# Test_board_-_MCP73871.net
KiCad netlist of a schematic drawn in EAGLE
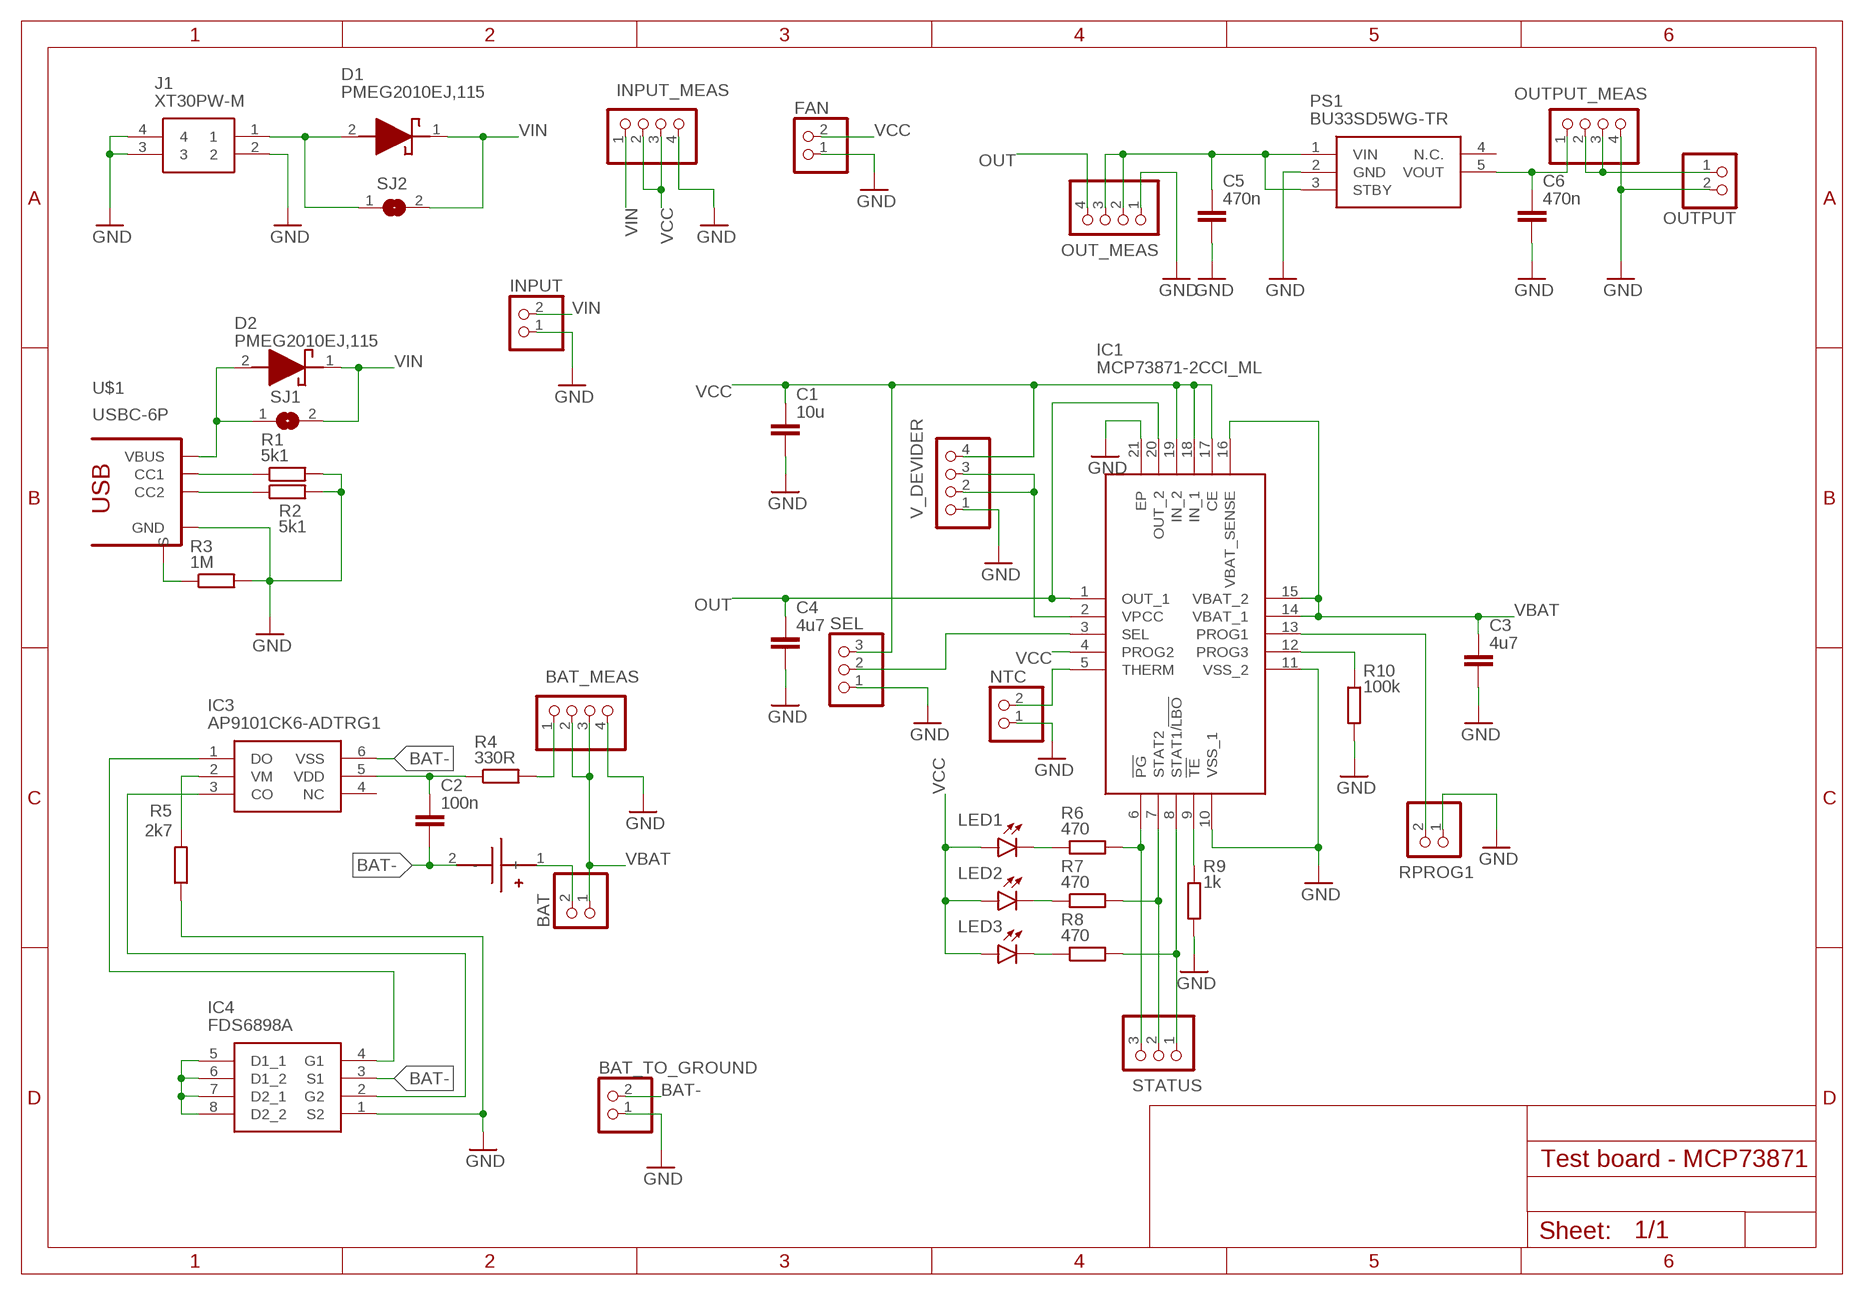
[diagram p0: schematic, sheet 1]

(export (version "E")
  (design (tool "Eeschema 10.0.6"))
  (components
    (comp (ref "BAT")
      (value "PINHD-1X2")
      (footprint "eagle-import:1X02")
      (libsource (lib "eagle-import") (part "PINHD-1X2"))
    )
    (comp (ref "BAT_MEAS")
      (value "PINHD-1X4")
      (footprint "eagle-import:1X04")
      (libsource (lib "eagle-import") (part "PINHD-1X4"))
    )
    (comp (ref "BAT_TO_GROUND")
      (value "PINHD-1X2")
      (footprint "eagle-import:1X02")
      (libsource (lib "eagle-import") (part "PINHD-1X2"))
    )
    (comp (ref "C1")
      (value "10u")
      (footprint "eagle-import:C0805")
      (libsource (lib "eagle-import") (part "C-EUC0805"))
    )
    (comp (ref "C2")
      (value "100n")
      (footprint "eagle-import:C0805")
      (libsource (lib "eagle-import") (part "C-EUC0805"))
    )
    (comp (ref "C3")
      (value "4u7")
      (footprint "eagle-import:C0805")
      (libsource (lib "eagle-import") (part "C-EUC0805"))
    )
    (comp (ref "C4")
      (value "4u7")
      (footprint "eagle-import:C0805")
      (libsource (lib "eagle-import") (part "C-EUC0805"))
    )
    (comp (ref "C5")
      (value "470n")
      (footprint "eagle-import:C0805")
      (libsource (lib "eagle-import") (part "C-EUC0805"))
    )
    (comp (ref "C6")
      (value "470n")
      (footprint "eagle-import:C0805")
      (libsource (lib "eagle-import") (part "C-EUC0805"))
    )
    (comp (ref "D1")
      (value "PMEG2010EJ,115")
      (footprint "eagle-import:SODFL2512X80N")
      (fields (field (name "MOUSER_PART_NUMBER") "771-PMEG2010EJ-T/R"))
      (libsource (lib "eagle-import") (part "PMEG2010EJ,115"))
    )
    (comp (ref "D2")
      (value "PMEG2010EJ,115")
      (footprint "eagle-import:SODFL2512X80N")
      (fields (field (name "MOUSER_PART_NUMBER") "771-PMEG2010EJ-T/R"))
      (libsource (lib "eagle-import") (part "PMEG2010EJ,115"))
    )
    (comp (ref "FAN")
      (value "PINHD-1X2")
      (footprint "eagle-import:1X02")
      (libsource (lib "eagle-import") (part "PINHD-1X2"))
    )
    (comp (ref "IC1")
      (value "MCP73871-2CCI_ML")
      (footprint "eagle-import:QFN50P400X400X100-21N")
      (fields
        (field (name "ARROW_PART_NUMBER") "MCP73871-2CCI/ML")
        (field (name "MOUSER_PART_NUMBER") "579-MCP73871-2CCI/ML")
      )
      (libsource (lib "eagle-import") (part "MCP73871-2CCI_ML"))
    )
    (comp (ref "IC3")
      (value "AP9101CK6-ADTRG1")
      (footprint "eagle-import:SOT95P285X140-6N")
      (fields (field (name "MOUSER_PART_NUMBER") "621-AP9101CK6-ADTRG1"))
      (libsource (lib "eagle-import") (part "AP9101CK6-ADTRG1"))
    )
    (comp (ref "IC4")
      (value "FDS6898A")
      (footprint "eagle-import:SOIC127P600X175-8N")
      (fields (field (name "MOUSER_PART_NUMBER") "512-FDS6898A"))
      (libsource (lib "eagle-import") (part "FDS6898A"))
    )
    (comp (ref "INPUT")
      (value "PINHD-1X2")
      (footprint "eagle-import:1X02")
      (libsource (lib "eagle-import") (part "PINHD-1X2"))
    )
    (comp (ref "INPUT_MEAS")
      (value "PINHD-1X4")
      (footprint "eagle-import:1X04")
      (libsource (lib "eagle-import") (part "PINHD-1X4"))
    )
    (comp (ref "J1")
      (value "XT30PW-M")
      (footprint "eagle-import:XT30PWM")
      (libsource (lib "eagle-import") (part "XT30PW-M"))
    )
    (comp (ref "LED1")
      (value "!PG")
      (footprint "eagle-import:CHIPLED_0805")
      (libsource (lib "eagle-import") (part "LEDCHIPLED_0805"))
    )
    (comp (ref "LED2")
      (value "STAT2")
      (footprint "eagle-import:CHIPLED_0805")
      (libsource (lib "eagle-import") (part "LEDCHIPLED_0805"))
    )
    (comp (ref "LED3")
      (value "STAT1")
      (footprint "eagle-import:CHIPLED_0805")
      (libsource (lib "eagle-import") (part "LEDCHIPLED_0805"))
    )
    (comp (ref "NTC")
      (value "PINHD-1X2")
      (footprint "eagle-import:1X02")
      (libsource (lib "eagle-import") (part "PINHD-1X2"))
    )
    (comp (ref "OUTPUT")
      (value "PINHD-1X2")
      (footprint "eagle-import:1X02")
      (libsource (lib "eagle-import") (part "PINHD-1X2"))
    )
    (comp (ref "OUTPUT_MEAS")
      (value "PINHD-1X4")
      (footprint "eagle-import:1X04")
      (libsource (lib "eagle-import") (part "PINHD-1X4"))
    )
    (comp (ref "OUT_MEAS")
      (value "PINHD-1X4")
      (footprint "eagle-import:1X04")
      (libsource (lib "eagle-import") (part "PINHD-1X4"))
    )
    (comp (ref "PS1")
      (value "BU33SD5WG-TR")
      (footprint "eagle-import:SOT95P280X125-5N")
      (fields (field (name "MOUSER_PART_NUMBER") "755-BU33SD5WG-TR"))
      (libsource (lib "eagle-import") (part "BU33SD5WG-TR"))
    )
    (comp (ref "R1")
      (value "5k1")
      (footprint "eagle-import:R0805")
      (libsource (lib "eagle-import") (part "R-EU_R0805"))
    )
    (comp (ref "R2")
      (value "5k1")
      (footprint "eagle-import:R0805")
      (libsource (lib "eagle-import") (part "R-EU_R0805"))
    )
    (comp (ref "R3")
      (value "1M")
      (footprint "eagle-import:R0805")
      (libsource (lib "eagle-import") (part "R-EU_R0805"))
    )
    (comp (ref "R4")
      (value "330R")
      (footprint "eagle-import:R0805")
      (libsource (lib "eagle-import") (part "R-EU_R0805"))
    )
    (comp (ref "R5")
      (value "2k7")
      (footprint "eagle-import:R0805")
      (libsource (lib "eagle-import") (part "R-EU_R0805"))
    )
    (comp (ref "R6")
      (value "470")
      (footprint "eagle-import:R0805")
      (libsource (lib "eagle-import") (part "R-EU_R0805"))
    )
    (comp (ref "R7")
      (value "470")
      (footprint "eagle-import:R0805")
      (libsource (lib "eagle-import") (part "R-EU_R0805"))
    )
    (comp (ref "R8")
      (value "470")
      (footprint "eagle-import:R0805")
      (libsource (lib "eagle-import") (part "R-EU_R0805"))
    )
    (comp (ref "R9")
      (value "1k")
      (footprint "eagle-import:R0805")
      (libsource (lib "eagle-import") (part "R-EU_R0805"))
    )
    (comp (ref "R10")
      (value "100k")
      (footprint "eagle-import:R0805")
      (libsource (lib "eagle-import") (part "R-EU_R0805"))
    )
    (comp (ref "RPROG1")
      (value "PINHD-1X2")
      (footprint "eagle-import:1X02")
      (libsource (lib "eagle-import") (part "PINHD-1X2"))
    )
    (comp (ref "SEL")
      (value "PINHD-1X3")
      (footprint "eagle-import:1X03")
      (libsource (lib "eagle-import") (part "PINHD-1X3"))
    )
    (comp (ref "SJ1") (value "SJ") (footprint "eagle-import:SJ") (libsource (lib "eagle-import") (part "SJ")))
    (comp (ref "SJ2") (value "SJ") (footprint "eagle-import:SJ") (libsource (lib "eagle-import") (part "SJ")))
    (comp (ref "STATUS")
      (value "PINHD-1X3")
      (footprint "eagle-import:1X03")
      (libsource (lib "eagle-import") (part "PINHD-1X3"))
    )
    (comp (ref "U$1")
      (value "USBC-6P")
      (footprint "eagle-import:USCX-06FX-XXMX-01")
      (libsource (lib "eagle-import") (part "USBC-6P"))
    )
    (comp (ref "U$2")
      (value "BLOSSOM-BLM-18650-1PCS")
      (footprint "eagle-import:BLOSSOM-BLM-18650-1PCS")
      (libsource (lib "eagle-import") (part "BLOSSOM-BLM-18650-1PCS"))
    )
    (comp (ref "V_DEVIDER")
      (value "PINHD-1X4")
      (footprint "eagle-import:1X04")
      (libsource (lib "eagle-import") (part "PINHD-1X4"))
    )
  )
  (nets
    (net (code "1") (name "/OUT") (class "Default")
      (node (ref "C4") (pin "1") (pinfunction "1_1") (pintype "passive"))
      (node (ref "IC1") (pin "1") (pinfunction "OUT_1_1") (pintype "bidirectional"))
      (node (ref "IC1") (pin "20") (pinfunction "OUT_2_20") (pintype "bidirectional"))
      (node (ref "OUT_MEAS") (pin "4") (pinfunction "4_4") (pintype "passive"))
    )
    (net (code "2") (name "/VBAT") (class "Default")
      (node (ref "BAT") (pin "1") (pinfunction "1_1") (pintype "passive"))
      (node (ref "BAT_MEAS") (pin "2") (pinfunction "2_2") (pintype "passive"))
      (node (ref "BAT_MEAS") (pin "3") (pinfunction "3_3") (pintype "passive"))
      (node (ref "C3") (pin "1") (pinfunction "1_1") (pintype "passive"))
      (node (ref "IC1") (pin "14") (pinfunction "VBAT_1_14") (pintype "bidirectional"))
      (node (ref "IC1") (pin "15") (pinfunction "VBAT_2_15") (pintype "bidirectional"))
      (node (ref "IC1") (pin "16") (pinfunction "VBAT_SENSE_16") (pintype "bidirectional"))
    )
    (net (code "3") (name "/VCC") (class "Default")
      (node (ref "C1") (pin "1") (pinfunction "1_1") (pintype "passive"))
      (node (ref "FAN") (pin "2") (pinfunction "2_2") (pintype "passive"))
      (node (ref "IC1") (pin "17") (pinfunction "CE_17") (pintype "bidirectional"))
      (node (ref "IC1") (pin "18") (pinfunction "IN_1_18") (pintype "bidirectional"))
      (node (ref "IC1") (pin "19") (pinfunction "IN_2_19") (pintype "bidirectional"))
      (node (ref "IC1") (pin "4") (pinfunction "PROG2_4") (pintype "bidirectional"))
      (node (ref "INPUT_MEAS") (pin "2") (pinfunction "2_2") (pintype "passive"))
      (node (ref "INPUT_MEAS") (pin "3") (pinfunction "3_3") (pintype "passive"))
      (node (ref "LED1") (pin "A") (pinfunction "A_A") (pintype "passive"))
      (node (ref "LED2") (pin "A") (pinfunction "A_A") (pintype "passive"))
      (node (ref "LED3") (pin "A") (pinfunction "A_A") (pintype "passive"))
      (node (ref "SEL") (pin "3") (pinfunction "3_3") (pintype "passive"))
      (node (ref "V_DEVIDER") (pin "4") (pinfunction "4_4") (pintype "passive"))
    )
    (net (code "4") (name "/VIN") (class "Default")
      (node (ref "D1") (pin "1") (pinfunction "K_1") (pintype "bidirectional"))
      (node (ref "D2") (pin "1") (pinfunction "K_1") (pintype "bidirectional"))
      (node (ref "INPUT") (pin "2") (pinfunction "2_2") (pintype "passive"))
      (node (ref "INPUT_MEAS") (pin "1") (pinfunction "1_1") (pintype "passive"))
      (node (ref "SJ1") (pin "2") (pinfunction "2_2") (pintype "passive"))
      (node (ref "SJ2") (pin "2") (pinfunction "2_2") (pintype "passive"))
    )
    (net (code "5") (name "BAT-") (class "Default")
      (node (ref "BAT_TO_GROUND") (pin "2") (pinfunction "2_2") (pintype "passive"))
      (node (ref "C2") (pin "2") (pinfunction "2_2") (pintype "passive"))
      (node (ref "IC3") (pin "6") (pinfunction "VSS_6") (pintype "bidirectional"))
      (node (ref "IC4") (pin "3") (pinfunction "S1_3") (pintype "bidirectional"))
      (node (ref "U$2") (pin "2") (pinfunction "-_2") (pintype "bidirectional"))
    )
    (net (code "6") (name "GND") (class "Default")
      (node (ref "BAT_MEAS") (pin "4") (pinfunction "4_4") (pintype "passive"))
      (node (ref "BAT_TO_GROUND") (pin "1") (pinfunction "1_1") (pintype "passive"))
      (node (ref "C1") (pin "2") (pinfunction "2_2") (pintype "passive"))
      (node (ref "C3") (pin "2") (pinfunction "2_2") (pintype "passive"))
      (node (ref "C4") (pin "2") (pinfunction "2_2") (pintype "passive"))
      (node (ref "C5") (pin "2") (pinfunction "2_2") (pintype "passive"))
      (node (ref "C6") (pin "2") (pinfunction "2_2") (pintype "passive"))
      (node (ref "FAN") (pin "1") (pinfunction "1_1") (pintype "passive"))
      (node (ref "IC1") (pin "10") (pinfunction "VSS_1_10") (pintype "bidirectional"))
      (node (ref "IC1") (pin "11") (pinfunction "VSS_2_11") (pintype "bidirectional"))
      (node (ref "IC1") (pin "21") (pinfunction "EP_21") (pintype "bidirectional"))
      (node (ref "IC4") (pin "1") (pinfunction "S2_1") (pintype "bidirectional"))
      (node (ref "INPUT") (pin "1") (pinfunction "1_1") (pintype "passive"))
      (node (ref "INPUT_MEAS") (pin "4") (pinfunction "4_4") (pintype "passive"))
      (node (ref "J1") (pin "2") (pinfunction "2_2") (pintype "bidirectional"))
      (node (ref "J1") (pin "3") (pinfunction "3_3") (pintype "bidirectional"))
      (node (ref "J1") (pin "4") (pinfunction "4_4") (pintype "bidirectional"))
      (node (ref "NTC") (pin "1") (pinfunction "1_1") (pintype "passive"))
      (node (ref "OUTPUT") (pin "2") (pinfunction "2_2") (pintype "passive"))
      (node (ref "OUTPUT_MEAS") (pin "4") (pinfunction "4_4") (pintype "passive"))
      (node (ref "OUT_MEAS") (pin "1") (pinfunction "1_1") (pintype "passive"))
      (node (ref "PS1") (pin "2") (pinfunction "GND_2") (pintype "bidirectional"))
      (node (ref "R1") (pin "2") (pinfunction "2_2") (pintype "passive"))
      (node (ref "R10") (pin "2") (pinfunction "2_2") (pintype "passive"))
      (node (ref "R2") (pin "2") (pinfunction "2_2") (pintype "passive"))
      (node (ref "R3") (pin "2") (pinfunction "2_2") (pintype "passive"))
      (node (ref "R5") (pin "1") (pinfunction "1_1") (pintype "passive"))
      (node (ref "R9") (pin "2") (pinfunction "2_2") (pintype "passive"))
      (node (ref "RPROG1") (pin "1") (pinfunction "1_1") (pintype "passive"))
      (node (ref "SEL") (pin "1") (pinfunction "1_1") (pintype "passive"))
      (node (ref "U$1") (pin "GND1") (pinfunction "GND_GND1") (pintype "power_in"))
      (node (ref "U$1") (pin "GND2") (pinfunction "GND_GND2") (pintype "power_in"))
      (node (ref "V_DEVIDER") (pin "1") (pinfunction "1_1") (pintype "passive"))
    )
    (net (code "7") (name "Net-(BAT_MEAS-Pad1)") (class "Default")
      (node (ref "BAT_MEAS") (pin "1") (pinfunction "1_1") (pintype "passive"))
      (node (ref "R4") (pin "2") (pinfunction "2_2") (pintype "passive"))
    )
    (net (code "8") (name "Net-(D1-A)") (class "Default")
      (node (ref "D1") (pin "2") (pinfunction "A_2") (pintype "bidirectional"))
      (node (ref "J1") (pin "1") (pinfunction "1_1") (pintype "bidirectional"))
      (node (ref "SJ2") (pin "1") (pinfunction "1_1") (pintype "passive"))
    )
    (net (code "9") (name "Net-(D2-A)") (class "Default")
      (node (ref "D2") (pin "2") (pinfunction "A_2") (pintype "bidirectional"))
      (node (ref "SJ1") (pin "1") (pinfunction "1_1") (pintype "passive"))
      (node (ref "U$1") (pin "VBUS1") (pinfunction "VBUS_VBUS1") (pintype "power_in"))
      (node (ref "U$1") (pin "VBUS2") (pinfunction "VBUS_VBUS2") (pintype "power_in"))
    )
    (net (code "10") (name "Net-(IC1-PROG1)") (class "Default")
      (node (ref "IC1") (pin "13") (pinfunction "PROG1_13") (pintype "bidirectional"))
      (node (ref "RPROG1") (pin "2") (pinfunction "2_2") (pintype "passive"))
    )
    (net (code "11") (name "Net-(IC1-PROG3)") (class "Default")
      (node (ref "IC1") (pin "12") (pinfunction "PROG3_12") (pintype "bidirectional"))
      (node (ref "R10") (pin "1") (pinfunction "1_1") (pintype "passive"))
    )
    (net (code "12") (name "Net-(IC1-SEL)") (class "Default")
      (node (ref "IC1") (pin "3") (pinfunction "SEL_3") (pintype "bidirectional"))
      (node (ref "SEL") (pin "2") (pinfunction "2_2") (pintype "passive"))
    )
    (net (code "13") (name "Net-(IC1-STAT1{slash}~{LBO})") (class "Default")
      (node (ref "IC1") (pin "8") (pinfunction "STAT1/~{LBO}_8") (pintype "bidirectional"))
      (node (ref "R8") (pin "2") (pinfunction "2_2") (pintype "passive"))
      (node (ref "STATUS") (pin "1") (pinfunction "1_1") (pintype "passive"))
    )
    (net (code "14") (name "Net-(IC1-STAT2)") (class "Default")
      (node (ref "IC1") (pin "7") (pinfunction "STAT2_7") (pintype "bidirectional"))
      (node (ref "R7") (pin "2") (pinfunction "2_2") (pintype "passive"))
      (node (ref "STATUS") (pin "2") (pinfunction "2_2") (pintype "passive"))
    )
    (net (code "15") (name "Net-(IC1-THERM)") (class "Default")
      (node (ref "IC1") (pin "5") (pinfunction "THERM_5") (pintype "bidirectional"))
      (node (ref "NTC") (pin "2") (pinfunction "2_2") (pintype "passive"))
    )
    (net (code "16") (name "Net-(IC1-VPCC)") (class "Default")
      (node (ref "IC1") (pin "2") (pinfunction "VPCC_2") (pintype "bidirectional"))
      (node (ref "V_DEVIDER") (pin "2") (pinfunction "2_2") (pintype "passive"))
      (node (ref "V_DEVIDER") (pin "3") (pinfunction "3_3") (pintype "passive"))
    )
    (net (code "17") (name "Net-(IC1-~{PG})") (class "Default")
      (node (ref "IC1") (pin "6") (pinfunction "~{PG}_6") (pintype "bidirectional"))
      (node (ref "R6") (pin "2") (pinfunction "2_2") (pintype "passive"))
      (node (ref "STATUS") (pin "3") (pinfunction "3_3") (pintype "passive"))
    )
    (net (code "18") (name "Net-(IC1-~{TE})") (class "Default")
      (node (ref "IC1") (pin "9") (pinfunction "~{TE}_9") (pintype "bidirectional"))
      (node (ref "R9") (pin "1") (pinfunction "1_1") (pintype "passive"))
    )
    (net (code "19") (name "Net-(IC3-CO)") (class "Default")
      (node (ref "IC3") (pin "3") (pinfunction "CO_3") (pintype "bidirectional"))
      (node (ref "IC4") (pin "2") (pinfunction "G2_2") (pintype "bidirectional"))
    )
    (net (code "20") (name "Net-(IC3-DO)") (class "Default")
      (node (ref "IC3") (pin "1") (pinfunction "DO_1") (pintype "bidirectional"))
      (node (ref "IC4") (pin "4") (pinfunction "G1_4") (pintype "bidirectional"))
    )
    (net (code "21") (name "Net-(IC3-VDD)") (class "Default")
      (node (ref "C2") (pin "1") (pinfunction "1_1") (pintype "passive"))
      (node (ref "IC3") (pin "5") (pinfunction "VDD_5") (pintype "bidirectional"))
      (node (ref "R4") (pin "1") (pinfunction "1_1") (pintype "passive"))
    )
    (net (code "22") (name "Net-(IC3-VM)") (class "Default")
      (node (ref "IC3") (pin "2") (pinfunction "VM_2") (pintype "bidirectional"))
      (node (ref "R5") (pin "2") (pinfunction "2_2") (pintype "passive"))
    )
    (net (code "23") (name "Net-(IC4-D1_1)") (class "Default")
      (node (ref "IC4") (pin "5") (pinfunction "D1_1_5") (pintype "bidirectional"))
      (node (ref "IC4") (pin "6") (pinfunction "D1_2_6") (pintype "bidirectional"))
      (node (ref "IC4") (pin "7") (pinfunction "D2_1_7") (pintype "bidirectional"))
      (node (ref "IC4") (pin "8") (pinfunction "D2_2_8") (pintype "bidirectional"))
    )
    (net (code "24") (name "Net-(LED1-PadC)") (class "Default")
      (node (ref "LED1") (pin "C") (pinfunction "C_C") (pintype "passive"))
      (node (ref "R6") (pin "1") (pinfunction "1_1") (pintype "passive"))
    )
    (net (code "25") (name "Net-(LED2-PadC)") (class "Default")
      (node (ref "LED2") (pin "C") (pinfunction "C_C") (pintype "passive"))
      (node (ref "R7") (pin "1") (pinfunction "1_1") (pintype "passive"))
    )
    (net (code "26") (name "Net-(LED3-PadC)") (class "Default")
      (node (ref "LED3") (pin "C") (pinfunction "C_C") (pintype "passive"))
      (node (ref "R8") (pin "1") (pinfunction "1_1") (pintype "passive"))
    )
    (net (code "27") (name "Net-(OUTPUT-Pad1)") (class "Default")
      (node (ref "OUTPUT") (pin "1") (pinfunction "1_1") (pintype "passive"))
      (node (ref "OUTPUT_MEAS") (pin "2") (pinfunction "2_2") (pintype "passive"))
      (node (ref "OUTPUT_MEAS") (pin "3") (pinfunction "3_3") (pintype "passive"))
    )
    (net (code "28") (name "Net-(PS1-STBY)") (class "Default")
      (node (ref "C5") (pin "1") (pinfunction "1_1") (pintype "passive"))
      (node (ref "OUT_MEAS") (pin "2") (pinfunction "2_2") (pintype "passive"))
      (node (ref "OUT_MEAS") (pin "3") (pinfunction "3_3") (pintype "passive"))
      (node (ref "PS1") (pin "1") (pinfunction "VIN_1") (pintype "bidirectional"))
      (node (ref "PS1") (pin "3") (pinfunction "STBY_3") (pintype "bidirectional"))
    )
    (net (code "29") (name "Net-(PS1-VOUT)") (class "Default")
      (node (ref "C6") (pin "1") (pinfunction "1_1") (pintype "passive"))
      (node (ref "OUTPUT_MEAS") (pin "1") (pinfunction "1_1") (pintype "passive"))
      (node (ref "PS1") (pin "5") (pinfunction "VOUT_5") (pintype "bidirectional"))
    )
    (net (code "30") (name "Net-(R1-Pad1)") (class "Default")
      (node (ref "R1") (pin "1") (pinfunction "1_1") (pintype "passive"))
      (node (ref "U$1") (pin "CC1") (pinfunction "CC1_CC1") (pintype "bidirectional"))
    )
    (net (code "31") (name "Net-(R2-Pad1)") (class "Default")
      (node (ref "R2") (pin "1") (pinfunction "1_1") (pintype "passive"))
      (node (ref "U$1") (pin "CC2") (pinfunction "CC2_CC2") (pintype "bidirectional"))
    )
    (net (code "32") (name "Net-(R3-Pad1)") (class "Default")
      (node (ref "R3") (pin "1") (pinfunction "1_1") (pintype "passive"))
      (node (ref "U$1") (pin "SHIELD1") (pinfunction "S_SHIELD1") (pintype "passive"))
      (node (ref "U$1") (pin "SHIELD2") (pinfunction "S_SHIELD2") (pintype "passive"))
      (node (ref "U$1") (pin "SHIELD3") (pinfunction "S_SHIELD3") (pintype "passive"))
      (node (ref "U$1") (pin "SHIELD4") (pinfunction "S_SHIELD4") (pintype "passive"))
    )
    (net (code "33") (name "Net-(U$2-+)") (class "Default")
      (node (ref "BAT") (pin "2") (pinfunction "2_2") (pintype "passive"))
      (node (ref "U$2") (pin "1") (pinfunction "+_1") (pintype "bidirectional"))
    )
    (net (code "34") (name "unconnected-(IC3-NC-Pad4)") (class "Default")
      (node (ref "IC3") (pin "4") (pinfunction "NC_4") (pintype "no_connect"))
    )
    (net (code "35") (name "unconnected-(PS1-N.C.-Pad4)") (class "Default")
      (node (ref "PS1") (pin "4") (pinfunction "N.C._4") (pintype "no_connect"))
    )
  )
)
